# other.net
KiCad netlist of a schematic drawn in Altium Designer
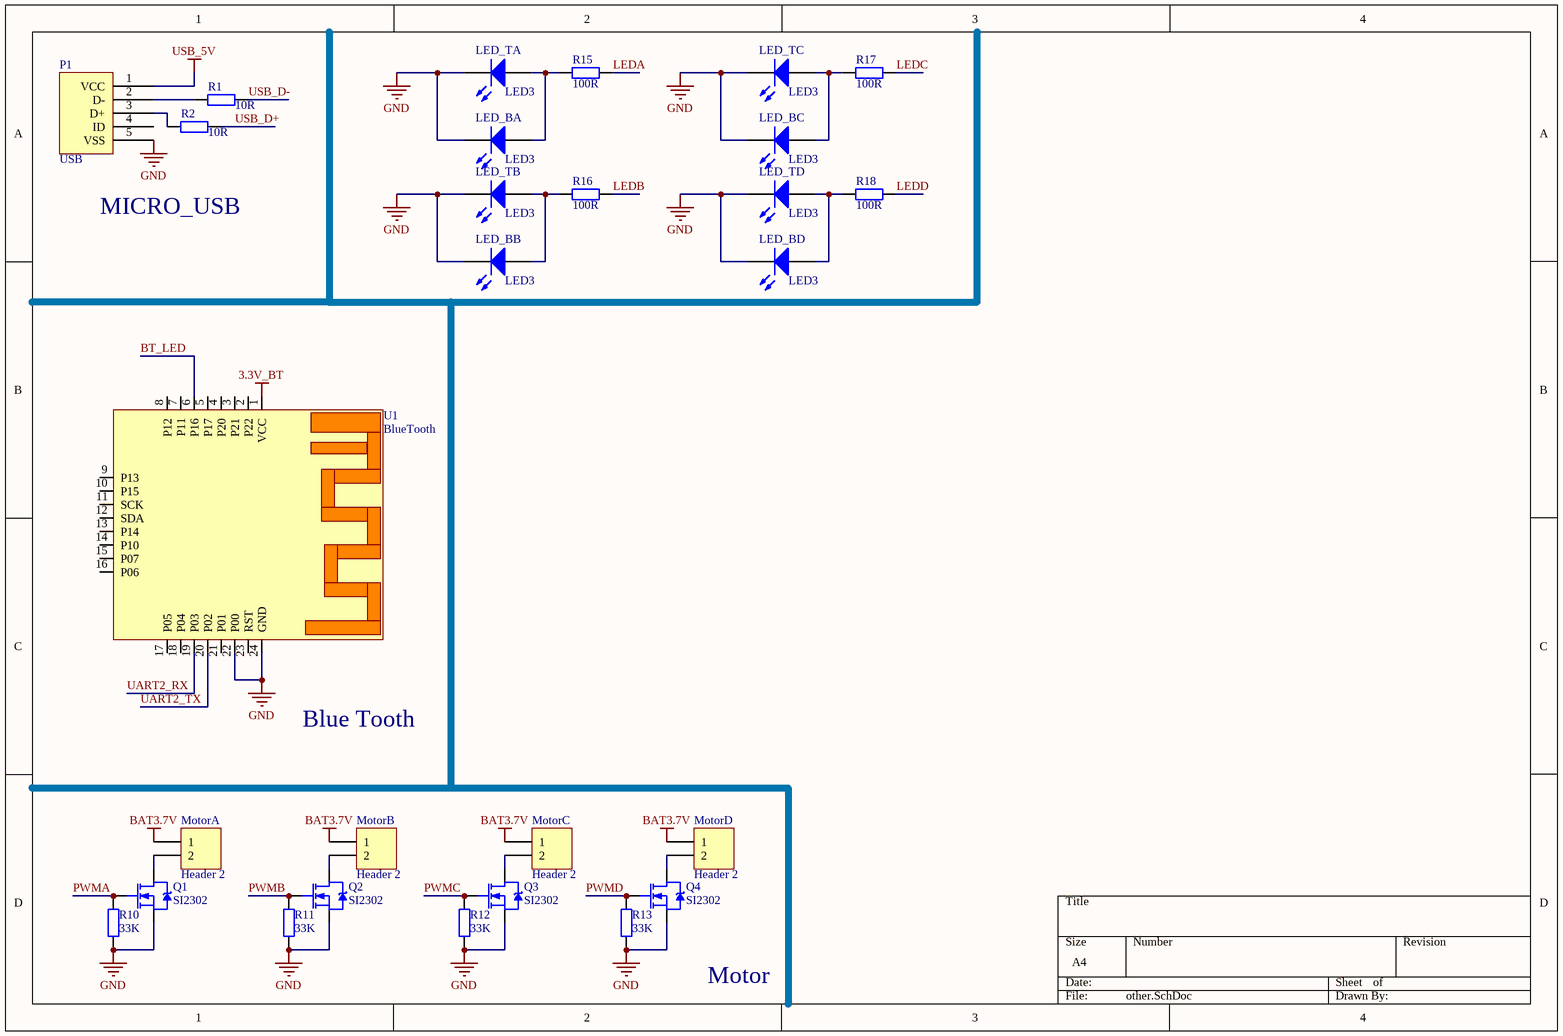
[diagram p0: other.SchDoc]

(export (version "E")
  (design (tool "Eeschema 10.0.6"))
  (components
    (comp (ref "LED_BA")
      (value "LED3")
      (footprint "LED_0603_RED")
      (description "Typical BLUE SiC LED")
      (fields (field (name "PUBLISHER") "Altium Limited"))
      (libsource (lib "Miscellaneous Devices") (part "LED3"))
    )
    (comp (ref "LED_BB")
      (value "LED3")
      (footprint "LED_0603_RED")
      (description "Typical BLUE SiC LED")
      (fields (field (name "PUBLISHER") "Altium Limited"))
      (libsource (lib "Miscellaneous Devices") (part "LED3"))
    )
    (comp (ref "LED_BC")
      (value "LED3")
      (footprint "LED_0603_RED")
      (description "Typical BLUE SiC LED")
      (fields (field (name "PUBLISHER") "Altium Limited"))
      (libsource (lib "Miscellaneous Devices") (part "LED3"))
    )
    (comp (ref "LED_BD")
      (value "LED3")
      (footprint "LED_0603_RED")
      (description "Typical BLUE SiC LED")
      (fields (field (name "PUBLISHER") "Altium Limited"))
      (libsource (lib "Miscellaneous Devices") (part "LED3"))
    )
    (comp (ref "LED_TA")
      (value "LED3")
      (footprint "LED_0603_RED")
      (description "Typical BLUE SiC LED")
      (fields (field (name "PUBLISHER") "Altium Limited"))
      (libsource (lib "Miscellaneous Devices") (part "LED3"))
    )
    (comp (ref "LED_TB")
      (value "LED3")
      (footprint "LED_0603_RED")
      (description "Typical BLUE SiC LED")
      (fields (field (name "PUBLISHER") "Altium Limited"))
      (libsource (lib "Miscellaneous Devices") (part "LED3"))
    )
    (comp (ref "LED_TC")
      (value "LED3")
      (footprint "LED_0603_RED")
      (description "Typical BLUE SiC LED")
      (fields (field (name "PUBLISHER") "Altium Limited"))
      (libsource (lib "Miscellaneous Devices") (part "LED3"))
    )
    (comp (ref "LED_TD")
      (value "LED3")
      (footprint "LED_0603_RED")
      (description "Typical BLUE SiC LED")
      (fields (field (name "PUBLISHER") "Altium Limited"))
      (libsource (lib "Miscellaneous Devices") (part "LED3"))
    )
    (comp (ref "MotorA")
      (value "Header 2")
      (footprint "HDR2 1.25mm")
      (description "Header, 2-Pin")
      (fields (field (name "PUBLISHER") "Altium Limited"))
      (libsource (lib "Miscellaneous Connectors") (part "Header 2"))
    )
    (comp (ref "MotorB")
      (value "Header 2")
      (footprint "HDR2 1.25mm")
      (description "Header, 2-Pin")
      (fields (field (name "PUBLISHER") "Altium Limited"))
      (libsource (lib "Miscellaneous Connectors") (part "Header 2"))
    )
    (comp (ref "MotorC")
      (value "Header 2")
      (footprint "HDR2 1.25mm")
      (description "Header, 2-Pin")
      (fields (field (name "PUBLISHER") "Altium Limited"))
      (libsource (lib "Miscellaneous Connectors") (part "Header 2"))
    )
    (comp (ref "MotorD")
      (value "Header 2")
      (footprint "HDR2 1.25mm")
      (description "Header, 2-Pin")
      (fields (field (name "PUBLISHER") "Altium Limited"))
      (libsource (lib "Miscellaneous Connectors") (part "Header 2"))
    )
    (comp (ref "P1") (value "USB") (footprint "USB_MICRO_M") (libsource (lib "mcu_board") (part "USB")))
    (comp (ref "Q1") (value "SI2302") (footprint "SI2302") (libsource (lib "quadcopter") (part "SI2302")))
    (comp (ref "Q2") (value "SI2302") (footprint "SI2302") (libsource (lib "quadcopter") (part "SI2302")))
    (comp (ref "Q3") (value "SI2302") (footprint "SI2302") (libsource (lib "quadcopter") (part "SI2302")))
    (comp (ref "Q4") (value "SI2302") (footprint "SI2302") (libsource (lib "quadcopter") (part "SI2302")))
    (comp (ref "R1")
      (value "10R")
      (footprint "R-0603")
      (description "Resistor")
      (fields (field (name "Comment") "Res2") (field (name "PUBLISHER") "Altium Limited"))
      (libsource (lib "") (part "Res2_1"))
    )
    (comp (ref "R2")
      (value "10R")
      (footprint "R-0603")
      (description "Resistor")
      (fields (field (name "Comment") "Res2") (field (name "PUBLISHER") "Altium Limited"))
      (libsource (lib "") (part "Res2_1"))
    )
    (comp (ref "R10")
      (value "33K")
      (footprint "R-0603")
      (description "Resistor")
      (fields (field (name "Comment") "Res2") (field (name "PUBLISHER") "Altium Limited"))
      (libsource (lib "") (part "Res2_1"))
    )
    (comp (ref "R11")
      (value "33K")
      (footprint "R-0603")
      (description "Resistor")
      (fields (field (name "Comment") "Res2") (field (name "PUBLISHER") "Altium Limited"))
      (libsource (lib "") (part "Res2_1"))
    )
    (comp (ref "R12")
      (value "33K")
      (footprint "R-0603")
      (description "Resistor")
      (fields (field (name "Comment") "Res2") (field (name "PUBLISHER") "Altium Limited"))
      (libsource (lib "") (part "Res2_1"))
    )
    (comp (ref "R13")
      (value "33K")
      (footprint "R-0603")
      (description "Resistor")
      (fields (field (name "Comment") "Res2") (field (name "PUBLISHER") "Altium Limited"))
      (libsource (lib "") (part "Res2_1"))
    )
    (comp (ref "R15")
      (value "100R")
      (footprint "R-0603")
      (description "Resistor")
      (fields (field (name "Comment") "Res2") (field (name "PUBLISHER") "Altium Limited"))
      (libsource (lib "Miscellaneous Devices") (part "Res2"))
    )
    (comp (ref "R16")
      (value "100R")
      (footprint "R-0603")
      (description "Resistor")
      (fields (field (name "Comment") "Res2") (field (name "PUBLISHER") "Altium Limited"))
      (libsource (lib "Miscellaneous Devices") (part "Res2"))
    )
    (comp (ref "R17")
      (value "100R")
      (footprint "R-0603")
      (description "Resistor")
      (fields (field (name "Comment") "Res2") (field (name "PUBLISHER") "Altium Limited"))
      (libsource (lib "Miscellaneous Devices") (part "Res2"))
    )
    (comp (ref "R18")
      (value "100R")
      (footprint "R-0603")
      (description "Resistor")
      (fields (field (name "Comment") "Res2") (field (name "PUBLISHER") "Altium Limited"))
      (libsource (lib "Miscellaneous Devices") (part "Res2"))
    )
    (comp (ref "U1")
      (value "BlueTooth")
      (footprint "BLE_CC2541")
      (libsource (lib "mcu_board") (part "CC2541-MOD"))
    )
  )
  (nets
    (net (code "1") (name "/BT_LED") (class "Default")
      (node (ref "U1") (pin "6") (pinfunction "P16_6") (pintype "passive"))
    )
    (net (code "2") (name "/LEDA") (class "Default")
      (node (ref "R15") (pin "2") (pinfunction "2_2") (pintype "passive"))
    )
    (net (code "3") (name "/LEDB") (class "Default")
      (node (ref "R16") (pin "2") (pinfunction "2_2") (pintype "passive"))
    )
    (net (code "4") (name "/LEDC") (class "Default")
      (node (ref "R17") (pin "2") (pinfunction "2_2") (pintype "passive"))
    )
    (net (code "5") (name "/LEDD") (class "Default")
      (node (ref "R18") (pin "2") (pinfunction "2_2") (pintype "passive"))
    )
    (net (code "6") (name "/PWMA") (class "Default")
      (node (ref "Q1") (pin "1") (pinfunction "G_1") (pintype "passive"))
      (node (ref "R10") (pin "2") (pinfunction "2_2") (pintype "passive"))
    )
    (net (code "7") (name "/PWMB") (class "Default")
      (node (ref "Q2") (pin "1") (pinfunction "G_1") (pintype "passive"))
      (node (ref "R11") (pin "2") (pinfunction "2_2") (pintype "passive"))
    )
    (net (code "8") (name "/PWMC") (class "Default")
      (node (ref "Q3") (pin "1") (pinfunction "G_1") (pintype "passive"))
      (node (ref "R12") (pin "2") (pinfunction "2_2") (pintype "passive"))
    )
    (net (code "9") (name "/PWMD") (class "Default")
      (node (ref "Q4") (pin "1") (pinfunction "G_1") (pintype "passive"))
      (node (ref "R13") (pin "2") (pinfunction "2_2") (pintype "passive"))
    )
    (net (code "10") (name "/UART2_RX") (class "Default")
      (node (ref "U1") (pin "19") (pinfunction "P03_19") (pintype "passive"))
    )
    (net (code "11") (name "/UART2_TX") (class "Default")
      (node (ref "U1") (pin "20") (pinfunction "P02_20") (pintype "passive"))
    )
    (net (code "12") (name "/USB_D+") (class "Default")
      (node (ref "R2") (pin "2") (pinfunction "2_2") (pintype "passive"))
    )
    (net (code "13") (name "/USB_D-") (class "Default")
      (node (ref "R1") (pin "2") (pinfunction "2_2") (pintype "passive"))
    )
    (net (code "14") (name "3.3V_BT") (class "Default")
      (node (ref "U1") (pin "1") (pinfunction "VCC_1") (pintype "passive"))
    )
    (net (code "15") (name "BAT3.7V") (class "Default")
      (node (ref "MotorA") (pin "1") (pinfunction "1_1") (pintype "passive"))
      (node (ref "MotorB") (pin "1") (pinfunction "1_1") (pintype "passive"))
      (node (ref "MotorC") (pin "1") (pinfunction "1_1") (pintype "passive"))
      (node (ref "MotorD") (pin "1") (pinfunction "1_1") (pintype "passive"))
    )
    (net (code "16") (name "GND") (class "Default")
      (node (ref "LED_BA") (pin "2") (pinfunction "K_2") (pintype "passive"))
      (node (ref "LED_BB") (pin "2") (pinfunction "K_2") (pintype "passive"))
      (node (ref "LED_BC") (pin "2") (pinfunction "K_2") (pintype "passive"))
      (node (ref "LED_BD") (pin "2") (pinfunction "K_2") (pintype "passive"))
      (node (ref "LED_TA") (pin "2") (pinfunction "K_2") (pintype "passive"))
      (node (ref "LED_TB") (pin "2") (pinfunction "K_2") (pintype "passive"))
      (node (ref "LED_TC") (pin "2") (pinfunction "K_2") (pintype "passive"))
      (node (ref "LED_TD") (pin "2") (pinfunction "K_2") (pintype "passive"))
      (node (ref "P1") (pin "5") (pinfunction "VSS_5") (pintype "passive"))
      (node (ref "Q1") (pin "2") (pinfunction "S_2") (pintype "passive"))
      (node (ref "Q2") (pin "2") (pinfunction "S_2") (pintype "passive"))
      (node (ref "Q3") (pin "2") (pinfunction "S_2") (pintype "passive"))
      (node (ref "Q4") (pin "2") (pinfunction "S_2") (pintype "passive"))
      (node (ref "R10") (pin "1") (pinfunction "1_1") (pintype "passive"))
      (node (ref "R11") (pin "1") (pinfunction "1_1") (pintype "passive"))
      (node (ref "R12") (pin "1") (pinfunction "1_1") (pintype "passive"))
      (node (ref "R13") (pin "1") (pinfunction "1_1") (pintype "passive"))
      (node (ref "U1") (pin "22") (pinfunction "P00_22") (pintype "passive"))
      (node (ref "U1") (pin "24") (pinfunction "GND_24") (pintype "passive"))
    )
    (net (code "17") (name "Net-(LED_BA-A)") (class "Default")
      (node (ref "LED_BA") (pin "1") (pinfunction "A_1") (pintype "passive"))
      (node (ref "LED_TA") (pin "1") (pinfunction "A_1") (pintype "passive"))
      (node (ref "R15") (pin "1") (pinfunction "1_1") (pintype "passive"))
    )
    (net (code "18") (name "Net-(LED_BB-A)") (class "Default")
      (node (ref "LED_BB") (pin "1") (pinfunction "A_1") (pintype "passive"))
      (node (ref "LED_TB") (pin "1") (pinfunction "A_1") (pintype "passive"))
      (node (ref "R16") (pin "1") (pinfunction "1_1") (pintype "passive"))
    )
    (net (code "19") (name "Net-(LED_BC-A)") (class "Default")
      (node (ref "LED_BC") (pin "1") (pinfunction "A_1") (pintype "passive"))
      (node (ref "LED_TC") (pin "1") (pinfunction "A_1") (pintype "passive"))
      (node (ref "R17") (pin "1") (pinfunction "1_1") (pintype "passive"))
    )
    (net (code "20") (name "Net-(LED_BD-A)") (class "Default")
      (node (ref "LED_BD") (pin "1") (pinfunction "A_1") (pintype "passive"))
      (node (ref "LED_TD") (pin "1") (pinfunction "A_1") (pintype "passive"))
      (node (ref "R18") (pin "1") (pinfunction "1_1") (pintype "passive"))
    )
    (net (code "21") (name "Net-(P1-D+)") (class "Default")
      (node (ref "P1") (pin "3") (pinfunction "D+_3") (pintype "passive"))
      (node (ref "R2") (pin "1") (pinfunction "1_1") (pintype "passive"))
    )
    (net (code "22") (name "Net-(P1-D-)") (class "Default")
      (node (ref "P1") (pin "2") (pinfunction "D-_2") (pintype "passive"))
      (node (ref "R1") (pin "1") (pinfunction "1_1") (pintype "passive"))
    )
    (net (code "23") (name "Net-(Q1-D)") (class "Default")
      (node (ref "MotorA") (pin "2") (pinfunction "2_2") (pintype "passive"))
      (node (ref "Q1") (pin "3") (pinfunction "D_3") (pintype "passive"))
    )
    (net (code "24") (name "Net-(Q2-D)") (class "Default")
      (node (ref "MotorB") (pin "2") (pinfunction "2_2") (pintype "passive"))
      (node (ref "Q2") (pin "3") (pinfunction "D_3") (pintype "passive"))
    )
    (net (code "25") (name "Net-(Q3-D)") (class "Default")
      (node (ref "MotorC") (pin "2") (pinfunction "2_2") (pintype "passive"))
      (node (ref "Q3") (pin "3") (pinfunction "D_3") (pintype "passive"))
    )
    (net (code "26") (name "Net-(Q4-D)") (class "Default")
      (node (ref "MotorD") (pin "2") (pinfunction "2_2") (pintype "passive"))
      (node (ref "Q4") (pin "3") (pinfunction "D_3") (pintype "passive"))
    )
    (net (code "27") (name "USB_5V") (class "Default")
      (node (ref "P1") (pin "1") (pinfunction "VCC_1") (pintype "passive"))
    )
    (net (code "28") (name "unconnected-(P1-ID-Pad4)") (class "Default")
      (node (ref "P1") (pin "4") (pinfunction "ID_4") (pintype "passive"))
    )
    (net (code "29") (name "unconnected-(U1-P01-Pad21)") (class "Default")
      (node (ref "U1") (pin "21") (pinfunction "P01_21") (pintype "passive"))
    )
    (net (code "30") (name "unconnected-(U1-P04-Pad18)") (class "Default")
      (node (ref "U1") (pin "18") (pinfunction "P04_18") (pintype "passive"))
    )
    (net (code "31") (name "unconnected-(U1-P05-Pad17)") (class "Default")
      (node (ref "U1") (pin "17") (pinfunction "P05_17") (pintype "passive"))
    )
    (net (code "32") (name "unconnected-(U1-P06-Pad16)") (class "Default")
      (node (ref "U1") (pin "16") (pinfunction "P06_16") (pintype "passive"))
    )
    (net (code "33") (name "unconnected-(U1-P07-Pad15)") (class "Default")
      (node (ref "U1") (pin "15") (pinfunction "P07_15") (pintype "passive"))
    )
    (net (code "34") (name "unconnected-(U1-P10-Pad14)") (class "Default")
      (node (ref "U1") (pin "14") (pinfunction "P10_14") (pintype "passive"))
    )
    (net (code "35") (name "unconnected-(U1-P11-Pad7)") (class "Default")
      (node (ref "U1") (pin "7") (pinfunction "P11_7") (pintype "passive"))
    )
    (net (code "36") (name "unconnected-(U1-P12-Pad8)") (class "Default")
      (node (ref "U1") (pin "8") (pinfunction "P12_8") (pintype "passive"))
    )
    (net (code "37") (name "unconnected-(U1-P13-Pad9)") (class "Default")
      (node (ref "U1") (pin "9") (pinfunction "P13_9") (pintype "passive"))
    )
    (net (code "38") (name "unconnected-(U1-P14-Pad13)") (class "Default")
      (node (ref "U1") (pin "13") (pinfunction "P14_13") (pintype "passive"))
    )
    (net (code "39") (name "unconnected-(U1-P15-Pad10)") (class "Default")
      (node (ref "U1") (pin "10") (pinfunction "P15_10") (pintype "passive"))
    )
    (net (code "40") (name "unconnected-(U1-P17-Pad5)") (class "Default")
      (node (ref "U1") (pin "5") (pinfunction "P17_5") (pintype "passive"))
    )
    (net (code "41") (name "unconnected-(U1-P20-Pad4)") (class "Default")
      (node (ref "U1") (pin "4") (pinfunction "P20_4") (pintype "passive"))
    )
    (net (code "42") (name "unconnected-(U1-P21-Pad3)") (class "Default")
      (node (ref "U1") (pin "3") (pinfunction "P21_3") (pintype "passive"))
    )
    (net (code "43") (name "unconnected-(U1-P22-Pad2)") (class "Default")
      (node (ref "U1") (pin "2") (pinfunction "P22_2") (pintype "passive"))
    )
    (net (code "44") (name "unconnected-(U1-RST-Pad23)") (class "Default")
      (node (ref "U1") (pin "23") (pinfunction "RST_23") (pintype "passive"))
    )
    (net (code "45") (name "unconnected-(U1-SCK-Pad11)") (class "Default")
      (node (ref "U1") (pin "11") (pinfunction "SCK_11") (pintype "passive"))
    )
    (net (code "46") (name "unconnected-(U1-SDA-Pad12)") (class "Default")
      (node (ref "U1") (pin "12") (pinfunction "SDA_12") (pintype "passive"))
    )
  )
)
